# modular-main.net
KiCad netlist of a schematic drawn in EAGLE
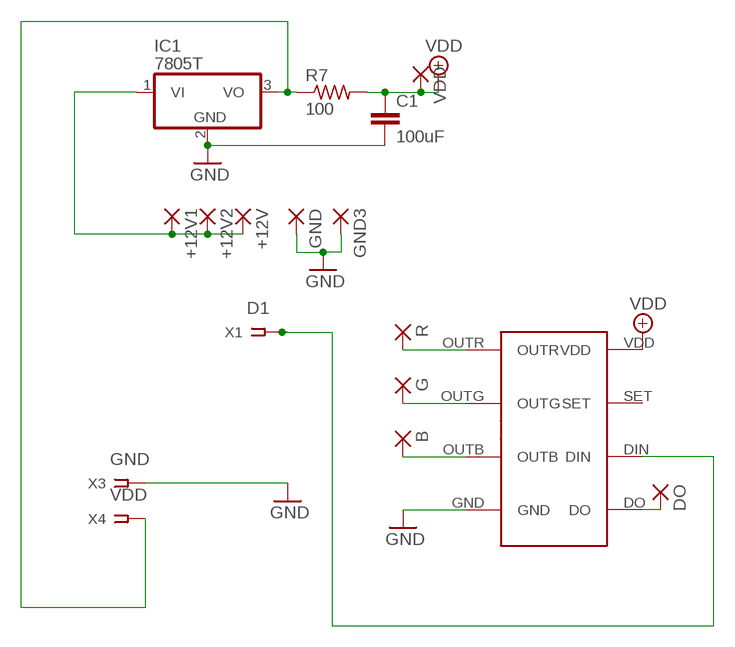
[diagram p0: schematic, sheet 1]

(export (version "E")
  (design (tool "Eeschema 10.0.6"))
  (components
    (comp (ref "+12V")
      (value "SMD5")
      (footprint "eagle-import:SMD2,54-5,08")
      (libsource (lib "eagle-import") (part "SMD5"))
    )
    (comp (ref "+12V1")
      (value "SMD5")
      (footprint "eagle-import:SMD2,54-5,08")
      (libsource (lib "eagle-import") (part "SMD5"))
    )
    (comp (ref "+12V2")
      (value "SMD5")
      (footprint "eagle-import:SMD2,54-5,08")
      (libsource (lib "eagle-import") (part "SMD5"))
    )
    (comp (ref "0")
      (value "WS2811")
      (footprint "eagle-import:SOP8")
      (libsource (lib "eagle-import") (part "WS2811"))
    )
    (comp (ref "B")
      (value "SMD5")
      (footprint "eagle-import:SMD2,54-5,08")
      (libsource (lib "eagle-import") (part "SMD5"))
    )
    (comp (ref "C1")
      (value "100uF")
      (footprint "eagle-import:C0805")
      (libsource (lib "eagle-import") (part "C-EUC0805"))
    )
    (comp (ref "DO")
      (value "SMD5")
      (footprint "eagle-import:SMD2,54-5,08")
      (libsource (lib "eagle-import") (part "SMD5"))
    )
    (comp (ref "G")
      (value "SMD5")
      (footprint "eagle-import:SMD2,54-5,08")
      (libsource (lib "eagle-import") (part "SMD5"))
    )
    (comp (ref "GND")
      (value "SMD5")
      (footprint "eagle-import:SMD2,54-5,08")
      (libsource (lib "eagle-import") (part "SMD5"))
    )
    (comp (ref "GND3")
      (value "SMD5")
      (footprint "eagle-import:SMD2,54-5,08")
      (libsource (lib "eagle-import") (part "SMD5"))
    )
    (comp (ref "IC1")
      (value "7805T")
      (footprint "eagle-import:TO220H")
      (libsource (lib "eagle-import") (part "78T05"))
    )
    (comp (ref "R")
      (value "SMD5")
      (footprint "eagle-import:SMD2,54-5,08")
      (libsource (lib "eagle-import") (part "SMD5"))
    )
    (comp (ref "R7")
      (value "100")
      (footprint "eagle-import:R0805")
      (libsource (lib "eagle-import") (part "R-US_R0805"))
    )
    (comp (ref "VDD")
      (value "SMD5")
      (footprint "eagle-import:SMD2,54-5,08")
      (libsource (lib "eagle-import") (part "SMD5"))
    )
    (comp (ref "X1")
      (value "D1")
      (footprint "eagle-import:SSW-101-02-G-S")
      (fields (field (name "MF") "Samtec Inc.") (field (name "MPN") "SSW-101-02-G-S"))
      (libsource (lib "eagle-import") (part "SSW-101-02-G-S"))
    )
    (comp (ref "X3")
      (value "GND")
      (footprint "eagle-import:SSW-101-02-G-S")
      (fields (field (name "MF") "Samtec Inc.") (field (name "MPN") "SSW-101-02-G-S"))
      (libsource (lib "eagle-import") (part "SSW-101-02-G-S"))
    )
    (comp (ref "X4")
      (value "VDD")
      (footprint "eagle-import:SSW-101-02-G-S")
      (fields (field (name "MF") "Samtec Inc.") (field (name "MPN") "SSW-101-02-G-S"))
      (libsource (lib "eagle-import") (part "SSW-101-02-G-S"))
    )
  )
  (nets
    (net (code "1") (name "GND") (class "Default")
      (node (ref "0") (pin "GND") (pinfunction "GND_GND") (pintype "bidirectional"))
      (node (ref "C1") (pin "2") (pinfunction "2_2") (pintype "passive"))
      (node (ref "GND") (pin "1") (pinfunction "P_1") (pintype "passive"))
      (node (ref "GND3") (pin "1") (pinfunction "P_1") (pintype "passive"))
      (node (ref "IC1") (pin "2") (pinfunction "GND_2") (pintype "passive"))
      (node (ref "X3") (pin "1") (pinfunction "1_1") (pintype "passive"))
    )
    (net (code "2") (name "Net-(+12V-P)") (class "Default")
      (node (ref "+12V") (pin "1") (pinfunction "P_1") (pintype "passive"))
      (node (ref "+12V1") (pin "1") (pinfunction "P_1") (pintype "passive"))
      (node (ref "+12V2") (pin "1") (pinfunction "P_1") (pintype "passive"))
      (node (ref "IC1") (pin "1") (pinfunction "VI_1") (pintype "input"))
    )
    (net (code "3") (name "Net-(0-PadDIN)") (class "Default")
      (node (ref "0") (pin "DIN") (pinfunction "DIN_DIN") (pintype "bidirectional"))
      (node (ref "X1") (pin "1") (pinfunction "1_1") (pintype "passive"))
    )
    (net (code "4") (name "Net-(B-P)") (class "Default")
      (node (ref "0") (pin "OUTB") (pinfunction "OUTB_OUTB") (pintype "bidirectional"))
      (node (ref "B") (pin "1") (pinfunction "P_1") (pintype "passive"))
    )
    (net (code "5") (name "Net-(DO-P)") (class "Default")
      (node (ref "0") (pin "DO") (pinfunction "DO_DO") (pintype "bidirectional"))
      (node (ref "DO") (pin "1") (pinfunction "P_1") (pintype "passive"))
    )
    (net (code "6") (name "Net-(G-P)") (class "Default")
      (node (ref "0") (pin "OUTG") (pinfunction "OUTG_OUTG") (pintype "bidirectional"))
      (node (ref "G") (pin "1") (pinfunction "P_1") (pintype "passive"))
    )
    (net (code "7") (name "Net-(IC1-VO)") (class "Default")
      (node (ref "IC1") (pin "3") (pinfunction "VO_3") (pintype "passive"))
      (node (ref "R7") (pin "1") (pinfunction "1_1") (pintype "passive"))
      (node (ref "X4") (pin "1") (pinfunction "1_1") (pintype "passive"))
    )
    (net (code "8") (name "Net-(R-P)") (class "Default")
      (node (ref "0") (pin "OUTR") (pinfunction "OUTR_OUTR") (pintype "bidirectional"))
      (node (ref "R") (pin "1") (pinfunction "P_1") (pintype "passive"))
    )
    (net (code "9") (name "VDD") (class "Default")
      (node (ref "0") (pin "VDD") (pinfunction "VDD_VDD") (pintype "bidirectional"))
      (node (ref "C1") (pin "1") (pinfunction "1_1") (pintype "passive"))
      (node (ref "R7") (pin "2") (pinfunction "2_2") (pintype "passive"))
      (node (ref "VDD") (pin "1") (pinfunction "P_1") (pintype "passive"))
    )
    (net (code "10") (name "unconnected-(0-PadSET)") (class "Default")
      (node (ref "0") (pin "SET") (pinfunction "SET_SET") (pintype "bidirectional"))
    )
  )
)
